# BMS_AFE_-_Connectors.net
KiCad netlist of a schematic drawn in Altium Designer
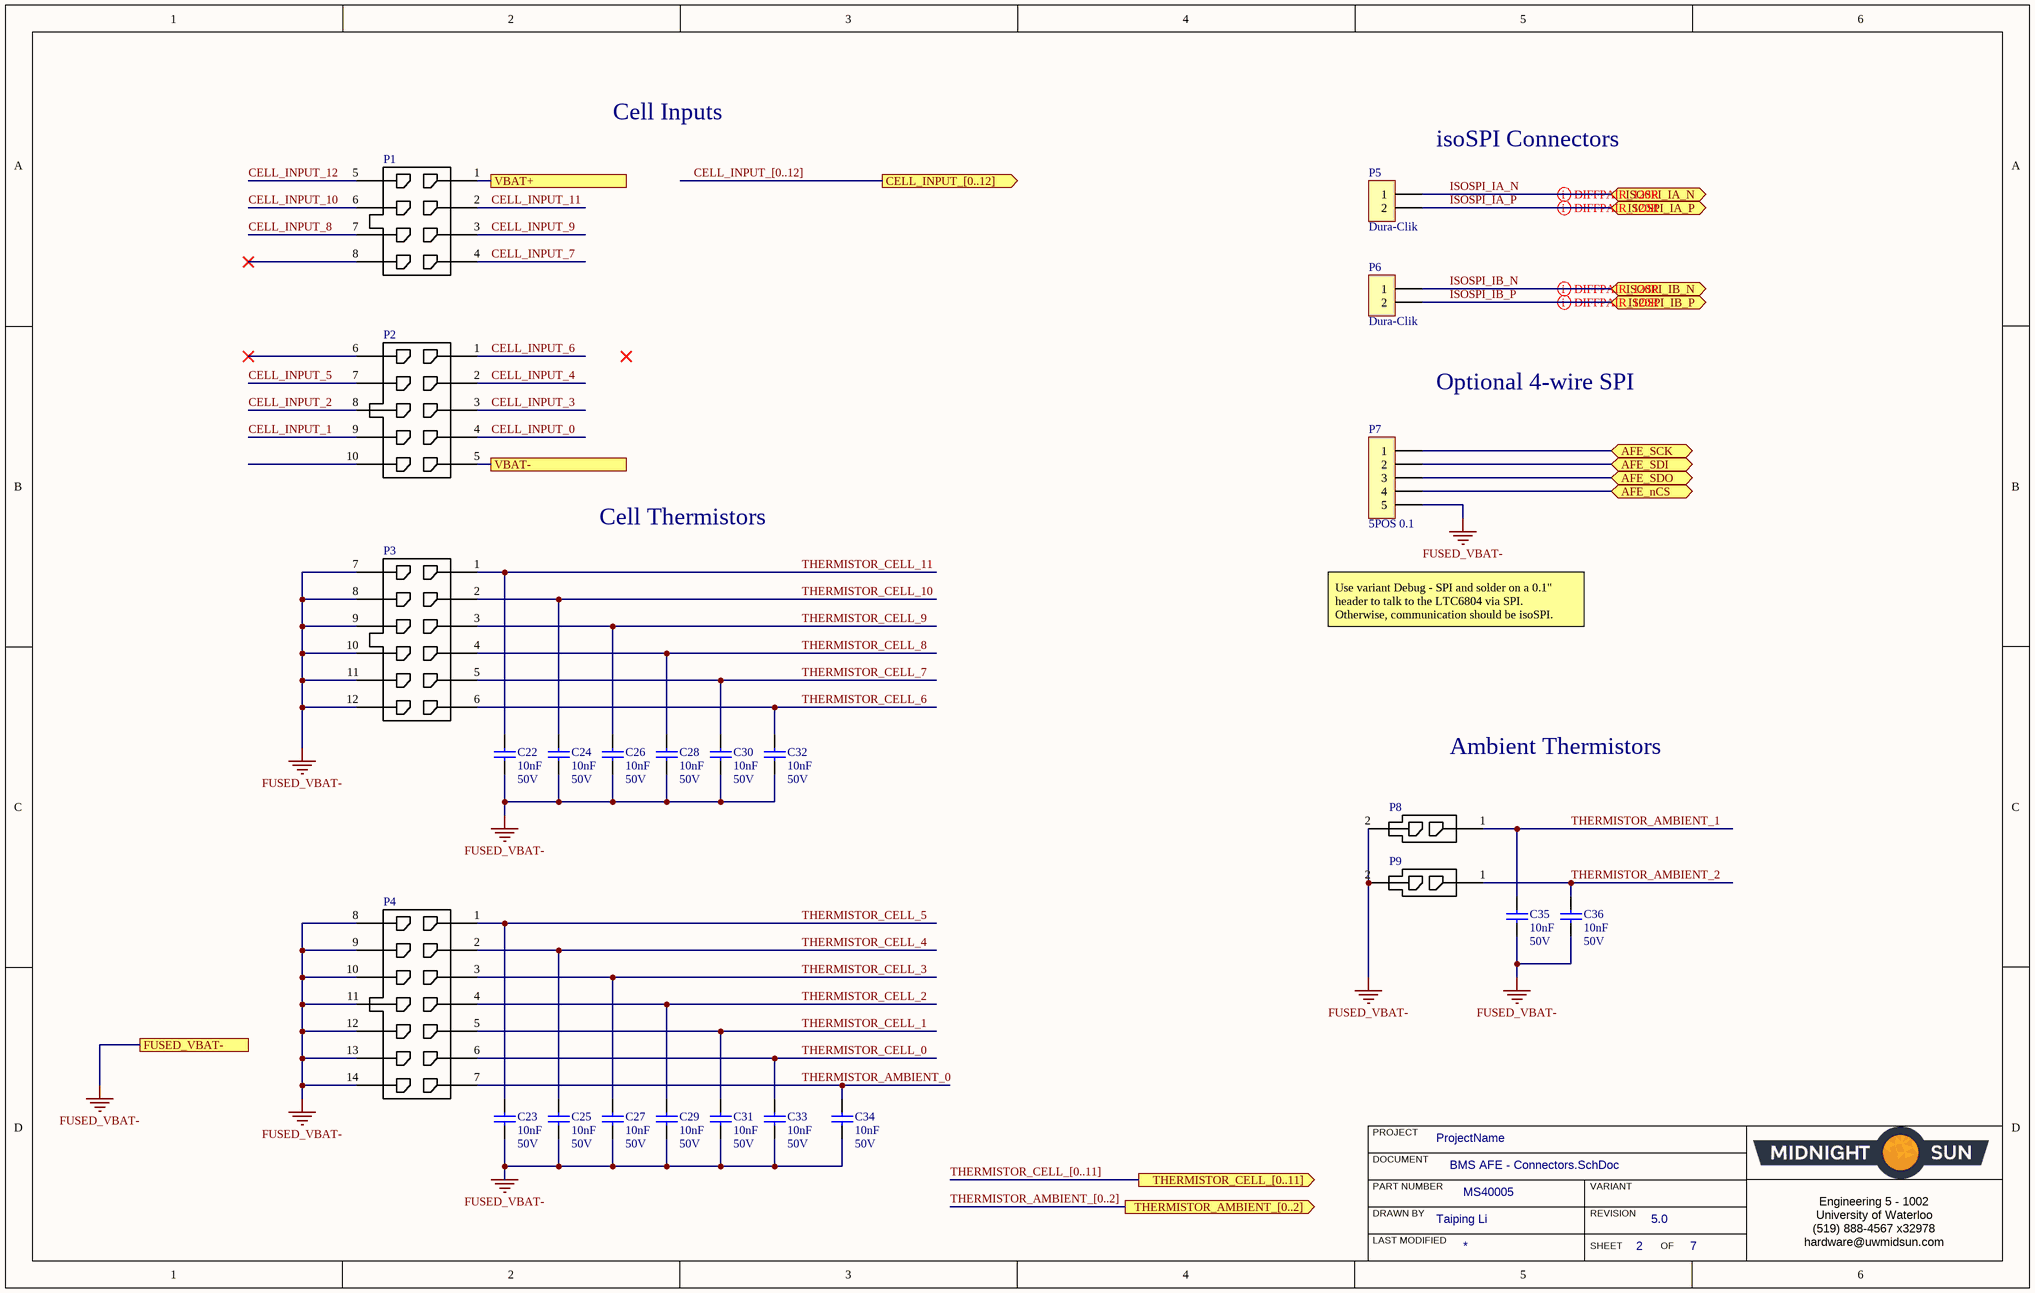
[diagram p0: BMS AFE - Connectors.SchDoc]

(export (version "E")
  (design (tool "Eeschema 10.0.6"))
  (components
    (comp (ref "C22")
      (value "CAP CER 10nF 50V 5% X7R 0603")
      (footprint "CAP, 0603")
      (description "10000pF ±5% 50V Ceramic Capacitor U2J 0603 (1608 Metric)")
      (fields
        (field (name "TOLERANCE") "±5%")
        (field (name "CAPACITANCE") "10nF")
        (field (name "VOLTAGE") "50V")
      )
      (libsource (lib "Schematic Diagrams") (part "CAP CER 10nF 50V 5% X7R 0603"))
    )
    (comp (ref "C23")
      (value "CAP CER 10nF 50V 5% X7R 0603")
      (footprint "CAP, 0603")
      (description "10000pF ±5% 50V Ceramic Capacitor U2J 0603 (1608 Metric)")
      (fields
        (field (name "TOLERANCE") "±5%")
        (field (name "CAPACITANCE") "10nF")
        (field (name "VOLTAGE") "50V")
      )
      (libsource (lib "Schematic Diagrams") (part "CAP CER 10nF 50V 5% X7R 0603"))
    )
    (comp (ref "C24")
      (value "CAP CER 10nF 50V 5% X7R 0603")
      (footprint "CAP, 0603")
      (description "10000pF ±5% 50V Ceramic Capacitor U2J 0603 (1608 Metric)")
      (fields
        (field (name "TOLERANCE") "±5%")
        (field (name "CAPACITANCE") "10nF")
        (field (name "VOLTAGE") "50V")
      )
      (libsource (lib "Schematic Diagrams") (part "CAP CER 10nF 50V 5% X7R 0603"))
    )
    (comp (ref "C25")
      (value "CAP CER 10nF 50V 5% X7R 0603")
      (footprint "CAP, 0603")
      (description "10000pF ±5% 50V Ceramic Capacitor U2J 0603 (1608 Metric)")
      (fields
        (field (name "TOLERANCE") "±5%")
        (field (name "CAPACITANCE") "10nF")
        (field (name "VOLTAGE") "50V")
      )
      (libsource (lib "Schematic Diagrams") (part "CAP CER 10nF 50V 5% X7R 0603"))
    )
    (comp (ref "C26")
      (value "CAP CER 10nF 50V 5% X7R 0603")
      (footprint "CAP, 0603")
      (description "10000pF ±5% 50V Ceramic Capacitor U2J 0603 (1608 Metric)")
      (fields
        (field (name "TOLERANCE") "±5%")
        (field (name "CAPACITANCE") "10nF")
        (field (name "VOLTAGE") "50V")
      )
      (libsource (lib "Schematic Diagrams") (part "CAP CER 10nF 50V 5% X7R 0603"))
    )
    (comp (ref "C27")
      (value "CAP CER 10nF 50V 5% X7R 0603")
      (footprint "CAP, 0603")
      (description "10000pF ±5% 50V Ceramic Capacitor U2J 0603 (1608 Metric)")
      (fields
        (field (name "TOLERANCE") "±5%")
        (field (name "CAPACITANCE") "10nF")
        (field (name "VOLTAGE") "50V")
      )
      (libsource (lib "Schematic Diagrams") (part "CAP CER 10nF 50V 5% X7R 0603"))
    )
    (comp (ref "C28")
      (value "CAP CER 10nF 50V 5% X7R 0603")
      (footprint "CAP, 0603")
      (description "10000pF ±5% 50V Ceramic Capacitor U2J 0603 (1608 Metric)")
      (fields
        (field (name "TOLERANCE") "±5%")
        (field (name "CAPACITANCE") "10nF")
        (field (name "VOLTAGE") "50V")
      )
      (libsource (lib "Schematic Diagrams") (part "CAP CER 10nF 50V 5% X7R 0603"))
    )
    (comp (ref "C29")
      (value "CAP CER 10nF 50V 5% X7R 0603")
      (footprint "CAP, 0603")
      (description "10000pF ±5% 50V Ceramic Capacitor U2J 0603 (1608 Metric)")
      (fields
        (field (name "TOLERANCE") "±5%")
        (field (name "CAPACITANCE") "10nF")
        (field (name "VOLTAGE") "50V")
      )
      (libsource (lib "Schematic Diagrams") (part "CAP CER 10nF 50V 5% X7R 0603"))
    )
    (comp (ref "C30")
      (value "CAP CER 10nF 50V 5% X7R 0603")
      (footprint "CAP, 0603")
      (description "10000pF ±5% 50V Ceramic Capacitor U2J 0603 (1608 Metric)")
      (fields
        (field (name "TOLERANCE") "±5%")
        (field (name "CAPACITANCE") "10nF")
        (field (name "VOLTAGE") "50V")
      )
      (libsource (lib "Schematic Diagrams") (part "CAP CER 10nF 50V 5% X7R 0603"))
    )
    (comp (ref "C31")
      (value "CAP CER 10nF 50V 5% X7R 0603")
      (footprint "CAP, 0603")
      (description "10000pF ±5% 50V Ceramic Capacitor U2J 0603 (1608 Metric)")
      (fields
        (field (name "TOLERANCE") "±5%")
        (field (name "CAPACITANCE") "10nF")
        (field (name "VOLTAGE") "50V")
      )
      (libsource (lib "Schematic Diagrams") (part "CAP CER 10nF 50V 5% X7R 0603"))
    )
    (comp (ref "C32")
      (value "CAP CER 10nF 50V 5% X7R 0603")
      (footprint "CAP, 0603")
      (description "10000pF ±5% 50V Ceramic Capacitor U2J 0603 (1608 Metric)")
      (fields
        (field (name "TOLERANCE") "±5%")
        (field (name "CAPACITANCE") "10nF")
        (field (name "VOLTAGE") "50V")
      )
      (libsource (lib "Schematic Diagrams") (part "CAP CER 10nF 50V 5% X7R 0603"))
    )
    (comp (ref "C33")
      (value "CAP CER 10nF 50V 5% X7R 0603")
      (footprint "CAP, 0603")
      (description "10000pF ±5% 50V Ceramic Capacitor U2J 0603 (1608 Metric)")
      (fields
        (field (name "TOLERANCE") "±5%")
        (field (name "CAPACITANCE") "10nF")
        (field (name "VOLTAGE") "50V")
      )
      (libsource (lib "Schematic Diagrams") (part "CAP CER 10nF 50V 5% X7R 0603"))
    )
    (comp (ref "C34")
      (value "CAP CER 10nF 50V 5% X7R 0603")
      (footprint "CAP, 0603")
      (description "10000pF ±5% 50V Ceramic Capacitor U2J 0603 (1608 Metric)")
      (fields
        (field (name "TOLERANCE") "±5%")
        (field (name "CAPACITANCE") "10nF")
        (field (name "VOLTAGE") "50V")
      )
      (libsource (lib "Schematic Diagrams") (part "CAP CER 10nF 50V 5% X7R 0603"))
    )
    (comp (ref "C35")
      (value "CAP CER 10nF 50V 5% X7R 0603")
      (footprint "CAP, 0603")
      (description "10000pF ±5% 50V Ceramic Capacitor U2J 0603 (1608 Metric)")
      (fields
        (field (name "TOLERANCE") "±5%")
        (field (name "CAPACITANCE") "10nF")
        (field (name "VOLTAGE") "50V")
      )
      (libsource (lib "Schematic Diagrams") (part "CAP CER 10nF 50V 5% X7R 0603"))
    )
    (comp (ref "C36")
      (value "CAP CER 10nF 50V 5% X7R 0603")
      (footprint "CAP, 0603")
      (description "10000pF ±5% 50V Ceramic Capacitor U2J 0603 (1608 Metric)")
      (fields
        (field (name "TOLERANCE") "±5%")
        (field (name "CAPACITANCE") "10nF")
        (field (name "VOLTAGE") "50V")
      )
      (libsource (lib "Schematic Diagrams") (part "CAP CER 10nF 50V 5% X7R 0603"))
    )
    (comp (ref "P1")
      (value "CONN 8POS MICRO-FIT 3mm")
      (description "Connector Header Through Hole 6 position 0.118\" (3.00mm)")
      (fields
        (field (name "MANUFACTURER") "Molex, LLC")
        (field (name "MANUFACTURER PART NUMBER") "0430450827")
      )
      (libsource (lib "Schematic Diagrams") (part "CONN 8POS MICRO-FIT 3mm"))
    )
    (comp (ref "P2")
      (value "CONN 10POS MICRO-FIT 3mm")
      (footprint "CONN, 10POS MICRO-FIT 3mm")
      (description "Connector Header Through Hole 10 position 0.118\" (3.00mm)")
      (fields
        (field (name "MANUFACTURER") "Molex, LLC")
        (field (name "MANUFACTURER PART NUMBER") "0430451027")
      )
      (libsource (lib "Schematic Diagrams") (part "CONN 10POS MICRO-FIT 3mm"))
    )
    (comp (ref "P3")
      (value "CONN 12POS MICRO-FIT 3mm")
      (footprint "CONN, 12POS MICRO-FIT 3mm")
      (description "Connector Header Through Hole 12 position 0.118\" (3.00mm)")
      (fields
        (field (name "MANUFACTURER") "Molex, LLC")
        (field (name "MANUFACTURER PART NUMBER") "0430451227")
      )
      (libsource (lib "Schematic Diagrams") (part "CONN 12POS MICRO-FIT 3mm"))
    )
    (comp (ref "P4")
      (value "CONN 14POS MICRO-FIT 3mm")
      (footprint "CONN, 14POS MICRO-FIT 3mm")
      (description "Connector Header Through Hole 14 position 0.118\" (3.00mm)")
      (fields
        (field (name "MANUFACTURER") "Molex, LLC")
        (field (name "MANUFACTURER PART NUMBER") "0430451427")
      )
      (libsource (lib "Schematic Diagrams") (part "CONN 14POS MICRO-FIT 3mm"))
    )
    (comp (ref "P5")
      (value "Dura-Clik")
      (footprint "CONN, 2POS Dura-Click Vertical")
      (description "2 Positions Header, Shrouded Connector 0.079\" (2.00mm) Surface Mount, Vertical Tin")
      (fields
        (field (name "MANUFACTURER") "Molex, LLC")
        (field (name "MANUFACTURER PART NUMBER") "5600200220")
      )
      (libsource (lib "Schematic Diagrams") (part "CONN 2POS DURA-CLIK 0.079{dblquote} VERT"))
    )
    (comp (ref "P6")
      (value "Dura-Clik")
      (footprint "CONN, 2POS Dura-Click Vertical")
      (description "2 Positions Header, Shrouded Connector 0.079\" (2.00mm) Surface Mount, Vertical Tin")
      (fields
        (field (name "MANUFACTURER") "Molex, LLC")
        (field (name "MANUFACTURER PART NUMBER") "5600200220")
      )
      (libsource (lib "Schematic Diagrams") (part "CONN 2POS DURA-CLIK 0.079{dblquote} VERT"))
    )
    (comp (ref "P7")
      (value "5POS 0.1")
      (footprint "CONN, 5POS HEADR 0.1\"")
      (description "5 Positions Header, Breakaway Connector 0.100\" (2.54mm) Through Hole Tin")
      (libsource (lib "Schematic Diagrams") (part "CONN 5POS HEADR MALE 0.1in"))
    )
    (comp (ref "P8")
      (value "CONN 2POS MICRO-FIT 3mm")
      (footprint "CONN, 2POS MICRO-FIT")
      (description "Connector Header Through Hole 2 position")
      (fields (field (name "MANUFACTURER") "Molex") (field (name "MANUFACTURER PART NUMBER") "43045-0227"))
      (libsource (lib "Schematic Diagrams") (part "CONN 2POS MICRO-FIT 3mm"))
    )
    (comp (ref "P9")
      (value "CONN 2POS MICRO-FIT 3mm")
      (footprint "CONN, 2POS MICRO-FIT")
      (description "Connector Header Through Hole 2 position")
      (fields (field (name "MANUFACTURER") "Molex") (field (name "MANUFACTURER PART NUMBER") "43045-0227"))
      (libsource (lib "Schematic Diagrams") (part "CONN 2POS MICRO-FIT 3mm"))
    )
  )
  (nets
    (net (code "1") (name "/AFE_SCK") (class "Default")
      (node (ref "P7") (pin "1") (pinfunction "1_1") (pintype "passive"))
    )
    (net (code "2") (name "/AFE_SDI") (class "Default")
      (node (ref "P7") (pin "2") (pinfunction "2_2") (pintype "passive"))
    )
    (net (code "3") (name "/AFE_SDO") (class "Default")
      (node (ref "P7") (pin "3") (pinfunction "3_3") (pintype "passive"))
    )
    (net (code "4") (name "/AFE_nCS") (class "Default")
      (node (ref "P7") (pin "4") (pinfunction "4_4") (pintype "passive"))
    )
    (net (code "5") (name "/CELL_INPUT_0") (class "Default")
      (node (ref "P2") (pin "4") (pinfunction "4_4") (pintype "passive"))
    )
    (net (code "6") (name "/CELL_INPUT_1") (class "Default")
      (node (ref "P2") (pin "9") (pinfunction "9_9") (pintype "passive"))
    )
    (net (code "7") (name "/CELL_INPUT_2") (class "Default")
      (node (ref "P2") (pin "8") (pinfunction "8_8") (pintype "passive"))
    )
    (net (code "8") (name "/CELL_INPUT_3") (class "Default")
      (node (ref "P2") (pin "3") (pinfunction "3_3") (pintype "passive"))
    )
    (net (code "9") (name "/CELL_INPUT_4") (class "Default")
      (node (ref "P2") (pin "2") (pinfunction "2_2") (pintype "passive"))
    )
    (net (code "10") (name "/CELL_INPUT_5") (class "Default")
      (node (ref "P2") (pin "7") (pinfunction "7_7") (pintype "passive"))
    )
    (net (code "11") (name "/CELL_INPUT_6") (class "Default")
      (node (ref "P2") (pin "1") (pinfunction "1_1") (pintype "passive"))
    )
    (net (code "12") (name "/CELL_INPUT_7") (class "Default")
      (node (ref "P1") (pin "4") (pinfunction "4_4") (pintype "passive"))
    )
    (net (code "13") (name "/CELL_INPUT_8") (class "Default")
      (node (ref "P1") (pin "7") (pinfunction "7_7") (pintype "passive"))
    )
    (net (code "14") (name "/CELL_INPUT_9") (class "Default")
      (node (ref "P1") (pin "3") (pinfunction "3_3") (pintype "passive"))
    )
    (net (code "15") (name "/CELL_INPUT_10") (class "Default")
      (node (ref "P1") (pin "6") (pinfunction "6_6") (pintype "passive"))
    )
    (net (code "16") (name "/CELL_INPUT_11") (class "Default")
      (node (ref "P1") (pin "2") (pinfunction "2_2") (pintype "passive"))
    )
    (net (code "17") (name "/CELL_INPUT_12") (class "Default")
      (node (ref "P1") (pin "5") (pinfunction "5_5") (pintype "passive"))
    )
    (net (code "19") (name "/ISOSPI_IA_N") (class "Default")
      (node (ref "P5") (pin "1") (pinfunction "1_1") (pintype "passive"))
    )
    (net (code "20") (name "/ISOSPI_IA_P") (class "Default")
      (node (ref "P5") (pin "2") (pinfunction "2_2") (pintype "passive"))
    )
    (net (code "21") (name "/ISOSPI_IB_N") (class "Default")
      (node (ref "P6") (pin "1") (pinfunction "1_1") (pintype "passive"))
    )
    (net (code "22") (name "/ISOSPI_IB_P") (class "Default")
      (node (ref "P6") (pin "2") (pinfunction "2_2") (pintype "passive"))
    )
    (net (code "23") (name "/THERMISTOR_AMBIENT_0") (class "Default")
      (node (ref "C34") (pin "1") (pinfunction "1_1") (pintype "passive"))
      (node (ref "P4") (pin "7") (pinfunction "7_7") (pintype "passive"))
    )
    (net (code "24") (name "/THERMISTOR_AMBIENT_1") (class "Default")
      (node (ref "C35") (pin "1") (pinfunction "1_1") (pintype "passive"))
      (node (ref "P8") (pin "1") (pinfunction "1_1") (pintype "passive"))
    )
    (net (code "25") (name "/THERMISTOR_AMBIENT_2") (class "Default")
      (node (ref "C36") (pin "1") (pinfunction "1_1") (pintype "passive"))
      (node (ref "P9") (pin "1") (pinfunction "1_1") (pintype "passive"))
    )
    (net (code "27") (name "/THERMISTOR_CELL_0") (class "Default")
      (node (ref "C33") (pin "1") (pinfunction "1_1") (pintype "passive"))
      (node (ref "P4") (pin "6") (pinfunction "6_6") (pintype "passive"))
    )
    (net (code "28") (name "/THERMISTOR_CELL_1") (class "Default")
      (node (ref "C31") (pin "1") (pinfunction "1_1") (pintype "passive"))
      (node (ref "P4") (pin "5") (pinfunction "5_5") (pintype "passive"))
    )
    (net (code "29") (name "/THERMISTOR_CELL_2") (class "Default")
      (node (ref "C29") (pin "1") (pinfunction "1_1") (pintype "passive"))
      (node (ref "P4") (pin "4") (pinfunction "4_4") (pintype "passive"))
    )
    (net (code "30") (name "/THERMISTOR_CELL_3") (class "Default")
      (node (ref "C27") (pin "1") (pinfunction "1_1") (pintype "passive"))
      (node (ref "P4") (pin "3") (pinfunction "3_3") (pintype "passive"))
    )
    (net (code "31") (name "/THERMISTOR_CELL_4") (class "Default")
      (node (ref "C25") (pin "1") (pinfunction "1_1") (pintype "passive"))
      (node (ref "P4") (pin "2") (pinfunction "2_2") (pintype "passive"))
    )
    (net (code "32") (name "/THERMISTOR_CELL_5") (class "Default")
      (node (ref "C23") (pin "1") (pinfunction "1_1") (pintype "passive"))
      (node (ref "P4") (pin "1") (pinfunction "1_1") (pintype "passive"))
    )
    (net (code "33") (name "/THERMISTOR_CELL_6") (class "Default")
      (node (ref "C32") (pin "1") (pinfunction "1_1") (pintype "passive"))
      (node (ref "P3") (pin "6") (pinfunction "6_6") (pintype "passive"))
    )
    (net (code "34") (name "/THERMISTOR_CELL_7") (class "Default")
      (node (ref "C30") (pin "1") (pinfunction "1_1") (pintype "passive"))
      (node (ref "P3") (pin "5") (pinfunction "5_5") (pintype "passive"))
    )
    (net (code "35") (name "/THERMISTOR_CELL_8") (class "Default")
      (node (ref "C28") (pin "1") (pinfunction "1_1") (pintype "passive"))
      (node (ref "P3") (pin "4") (pinfunction "4_4") (pintype "passive"))
    )
    (net (code "36") (name "/THERMISTOR_CELL_9") (class "Default")
      (node (ref "C26") (pin "1") (pinfunction "1_1") (pintype "passive"))
      (node (ref "P3") (pin "3") (pinfunction "3_3") (pintype "passive"))
    )
    (net (code "37") (name "/THERMISTOR_CELL_10") (class "Default")
      (node (ref "C24") (pin "1") (pinfunction "1_1") (pintype "passive"))
      (node (ref "P3") (pin "2") (pinfunction "2_2") (pintype "passive"))
    )
    (net (code "38") (name "/THERMISTOR_CELL_11") (class "Default")
      (node (ref "C22") (pin "1") (pinfunction "1_1") (pintype "passive"))
      (node (ref "P3") (pin "1") (pinfunction "1_1") (pintype "passive"))
    )
    (net (code "40") (name "/VBAT+") (class "Default")
      (node (ref "P1") (pin "1") (pinfunction "1_1") (pintype "passive"))
    )
    (net (code "41") (name "/VBAT-") (class "Default")
      (node (ref "P2") (pin "5") (pinfunction "5_5") (pintype "passive"))
    )
    (net (code "42") (name "FUSED_VBAT-") (class "Default")
      (node (ref "C22") (pin "2") (pinfunction "2_2") (pintype "passive"))
      (node (ref "C23") (pin "2") (pinfunction "2_2") (pintype "passive"))
      (node (ref "C24") (pin "2") (pinfunction "2_2") (pintype "passive"))
      (node (ref "C25") (pin "2") (pinfunction "2_2") (pintype "passive"))
      (node (ref "C26") (pin "2") (pinfunction "2_2") (pintype "passive"))
      (node (ref "C27") (pin "2") (pinfunction "2_2") (pintype "passive"))
      (node (ref "C28") (pin "2") (pinfunction "2_2") (pintype "passive"))
      (node (ref "C29") (pin "2") (pinfunction "2_2") (pintype "passive"))
      (node (ref "C30") (pin "2") (pinfunction "2_2") (pintype "passive"))
      (node (ref "C31") (pin "2") (pinfunction "2_2") (pintype "passive"))
      (node (ref "C32") (pin "2") (pinfunction "2_2") (pintype "passive"))
      (node (ref "C33") (pin "2") (pinfunction "2_2") (pintype "passive"))
      (node (ref "C34") (pin "2") (pinfunction "2_2") (pintype "passive"))
      (node (ref "C35") (pin "2") (pinfunction "2_2") (pintype "passive"))
      (node (ref "C36") (pin "2") (pinfunction "2_2") (pintype "passive"))
      (node (ref "P3") (pin "10") (pinfunction "10_10") (pintype "passive"))
      (node (ref "P3") (pin "11") (pinfunction "11_11") (pintype "passive"))
      (node (ref "P3") (pin "12") (pinfunction "12_12") (pintype "passive"))
      (node (ref "P3") (pin "7") (pinfunction "7_7") (pintype "passive"))
      (node (ref "P3") (pin "8") (pinfunction "8_8") (pintype "passive"))
      (node (ref "P3") (pin "9") (pinfunction "9_9") (pintype "passive"))
      (node (ref "P4") (pin "10") (pinfunction "10_10") (pintype "passive"))
      (node (ref "P4") (pin "11") (pinfunction "11_11") (pintype "passive"))
      (node (ref "P4") (pin "12") (pinfunction "12_12") (pintype "passive"))
      (node (ref "P4") (pin "13") (pinfunction "13_13") (pintype "passive"))
      (node (ref "P4") (pin "14") (pinfunction "14_14") (pintype "passive"))
      (node (ref "P4") (pin "8") (pinfunction "8_8") (pintype "passive"))
      (node (ref "P4") (pin "9") (pinfunction "9_9") (pintype "passive"))
      (node (ref "P7") (pin "5") (pinfunction "5_5") (pintype "passive"))
      (node (ref "P8") (pin "2") (pinfunction "2_2") (pintype "passive"))
      (node (ref "P9") (pin "2") (pinfunction "2_2") (pintype "passive"))
    )
    (net (code "43") (name "unconnected-(P1-Pad8)") (class "Default")
      (node (ref "P1") (pin "8") (pinfunction "8_8") (pintype "passive+no_connect"))
    )
    (net (code "44") (name "unconnected-(P2-Pad6)") (class "Default")
      (node (ref "P2") (pin "6") (pinfunction "6_6") (pintype "passive+no_connect"))
    )
    (net (code "45") (name "unconnected-(P2-Pad10)") (class "Default")
      (node (ref "P2") (pin "10") (pinfunction "10_10") (pintype "passive"))
    )
  )
)
